# ConnectorsAndProtection.net
KiCad netlist of a schematic drawn in Altium Designer
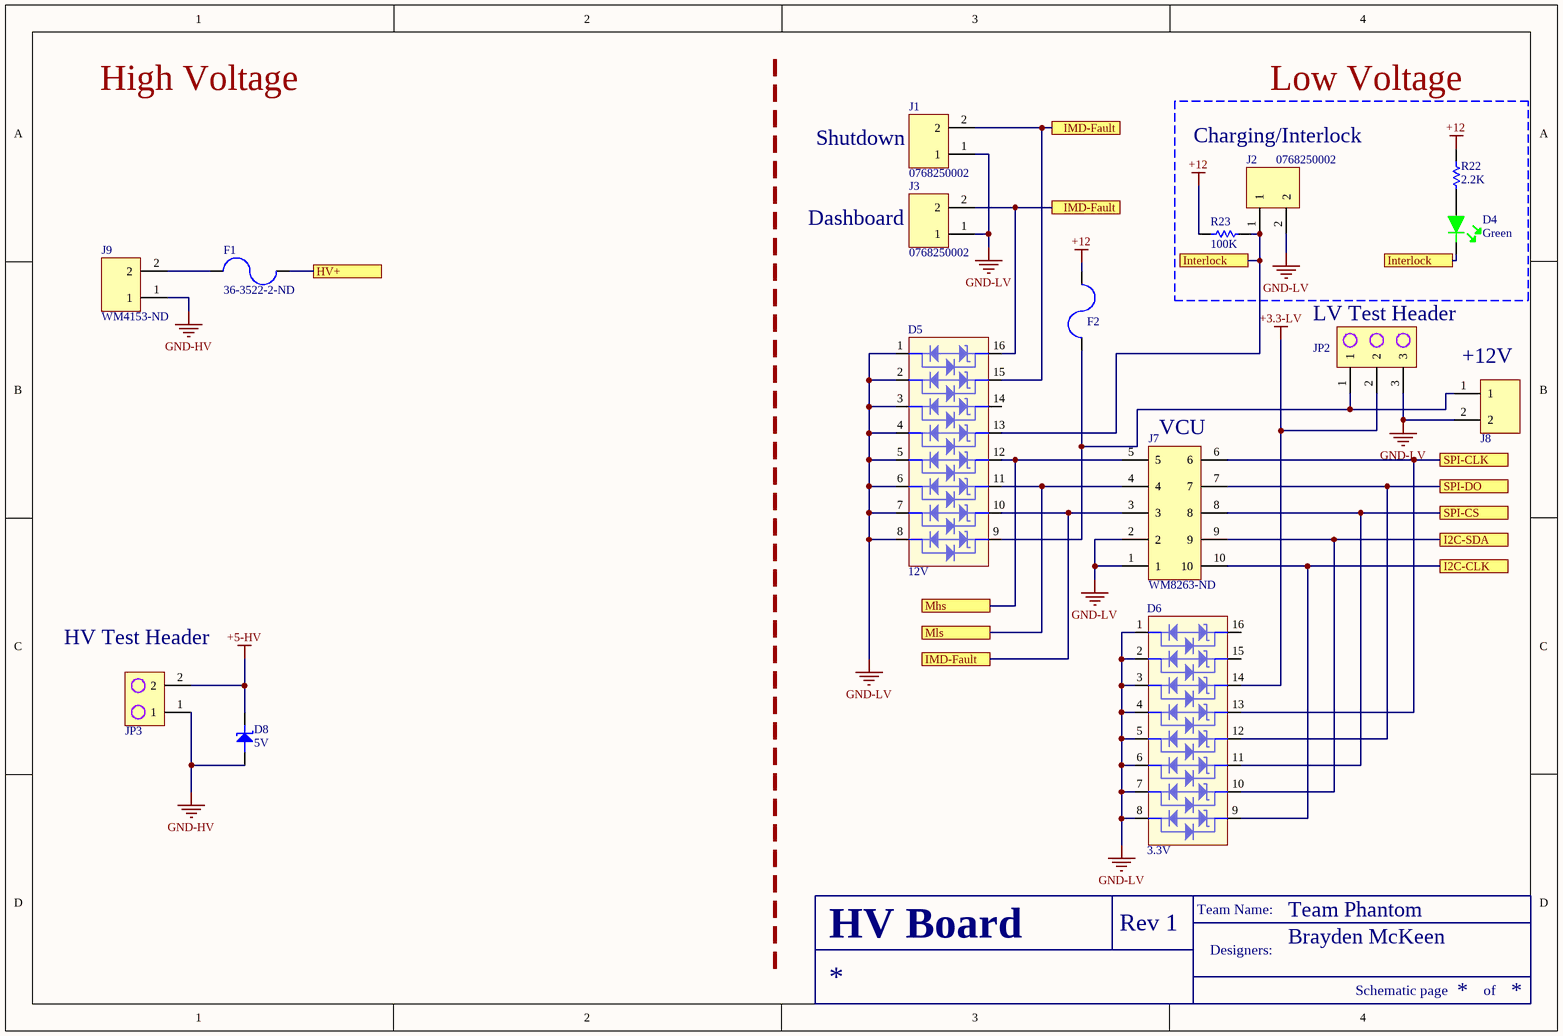
[diagram p0: ConnectorsAndProtection.SchDoc]

(export (version "E")
  (design (tool "Eeschema 10.0.6"))
  (components
    (comp (ref "D4")
      (value "Green")
      (footprint "LED-0603")
      (description "LED GREEN CLEAR 0603 SMD")
      (fields
        (field (name "MANUFACTURER") "Wurth Electronics")
        (field (name "MANUFACTURER PART NUMBER") "150060VS75000")
      )
      (libsource (lib "LEDs") (part "LED-Green"))
    )
    (comp (ref "D5")
      (value "12V")
      (footprint "16-SO")
      (description "PD 300W VWM 12VCJ 25PFPACKAGE SO")
      (libsource (lib "Diodes") (part "TVS-12V-X8"))
    )
    (comp (ref "D6")
      (value "3.3V")
      (footprint "16-SO")
      (description "PD 300W VWM 3.3VCJ 25PFPACKAGE S")
      (libsource (lib "Diodes") (part "TVS-3.3V-X8"))
    )
    (comp (ref "D8")
      (value "5V")
      (footprint "DIODE-SOD323")
      (description "TVS DIODE 5V SOD323")
      (fields
        (field (name "MANUFACTURER") "Nexperia")
        (field (name "MANUFACTURER PART NUMBER") "PESD5V0U1UA,115")
      )
      (libsource (lib "Diodes") (part "TVS-5V"))
    )
    (comp (ref "F1")
      (value "36-3522-2-ND")
      (footprint "Fuse Holder - 500V - 20A")
      (description "FUSE CLIP BLADE 500V 20A PCB")
      (libsource (lib "Misc") (part "Fuse Holder - 500V - 20A"))
    )
    (comp (ref "F2")
      (value "36-3555-2-ND")
      (footprint "Fuse Holder - 500V - 50A")
      (description "FUSE BLOCK BLADE 500V 50A PCB")
      (libsource (lib "Misc") (part "Fuse Holder - 500V - 50A"))
    )
    (comp (ref "J1")
      (value "0768250002")
      (footprint "2X1PIN")
      (description "CONN HEADER R/A 2POS")
      (fields (field (name "MANUFACTURER") "Molex") (field (name "MANUFACTURER PART NUMBER") "76825-0002"))
      (libsource (lib "Connectors") (part "2X1PIN"))
    )
    (comp (ref "J2")
      (value "0768250002")
      (footprint "2X1PIN")
      (description "CONN HEADER R/A 2POS")
      (fields (field (name "MANUFACTURER") "Molex") (field (name "MANUFACTURER PART NUMBER") "76825-0002"))
      (libsource (lib "") (part "2X1PIN_1"))
    )
    (comp (ref "J3")
      (value "0768250002")
      (footprint "2X1PIN")
      (description "CONN HEADER R/A 2POS")
      (fields (field (name "MANUFACTURER") "Molex") (field (name "MANUFACTURER PART NUMBER") "76825-0002"))
      (libsource (lib "Connectors") (part "2X1PIN"))
    )
    (comp (ref "J7")
      (value "WM8263-ND")
      (footprint "2X5PIN")
      (description "CONN HEADER R/A 10POS 2.54MM")
      (fields (field (name "MANUFACTURER") "Molex") (field (name "MANUFACTURER PART NUMBER") "90130-3110"))
      (libsource (lib "Connectors") (part "2X5PIN"))
    )
    (comp (ref "J8")
      (value "952-2900-ND")
      (footprint "2Pin-POWER")
      (description "CONN HEADER VERT 2POS 4MM 800V 40A")
      (libsource (lib "Connectors") (part "2PIN-POWER"))
    )
    (comp (ref "J9")
      (value "WM4153-ND")
      (footprint "2PIN")
      (description "CONN HEADER R/A 2POS 2.54MM")
      (fields (field (name "MANUFACTURER") "Molex") (field (name "MANUFACTURER PART NUMBER") "0705530106"))
      (libsource (lib "Connectors") (part "2PIN"))
    )
    (comp (ref "JP2")
      (value "732-5316-ND")
      (footprint "3PIN-JP")
      (description "CONN HEADER VERT 3POS 2.54MM")
      (libsource (lib "Connectors") (part "3PIN-TEST"))
    )
    (comp (ref "JP3")
      (value "732-5315-ND")
      (footprint "2PIN-JP")
      (description "CONN HEADER VERT 2POS 2.54MM")
      (libsource (lib "Connectors") (part "2PIN-TEST"))
    )
    (comp (ref "R22")
      (value "2.2K")
      (footprint "RES-0805")
      (description "RES SMD 2.2K OHM 1% 1/8W 0805")
      (fields
        (field (name "MANUFACTURER") "Yageo")
        (field (name "MANUFACTURER PART NUMBER") "RC0805FR-072K2L")
      )
      (libsource (lib "Resistors") (part "0805-2.2KR"))
    )
    (comp (ref "R23")
      (value "100K")
      (footprint "RES-0805")
      (description "RES SMD 100K OHM 1% 1/8W 0805")
      (fields
        (field (name "MANUFACTURER") "Yageo")
        (field (name "MANUFACTURER PART NUMBER") "RC0805FR-07100KL")
      )
      (libsource (lib "Resistors") (part "0805-100KR"))
    )
  )
  (nets
    (net (code "1") (name "+3.3-LV") (class "Default")
      (node (ref "D6") (pin "14") (pinfunction "14_14") (pintype "passive"))
      (node (ref "JP2") (pin "2") (pinfunction "2_2") (pintype "passive"))
    )
    (net (code "2") (name "+5-HV") (class "Default")
      (node (ref "D8") (pin "1") (pinfunction "1_1") (pintype "passive"))
      (node (ref "JP3") (pin "2") (pinfunction "2_2") (pintype "passive"))
    )
    (net (code "3") (name "+12") (class "Default")
      (node (ref "F2") (pin "2") (pinfunction "2_2") (pintype "passive"))
      (node (ref "R22") (pin "1") (pinfunction "1_1") (pintype "passive"))
      (node (ref "R23") (pin "1") (pinfunction "1_1") (pintype "passive"))
    )
    (net (code "4") (name "/HV+") (class "Default")
      (node (ref "F1") (pin "2") (pinfunction "2_2") (pintype "passive"))
    )
    (net (code "5") (name "/I2C-CLK") (class "Default")
      (node (ref "D6") (pin "9") (pinfunction "9_9") (pintype "passive"))
      (node (ref "J7") (pin "10") (pinfunction "10_10") (pintype "passive"))
    )
    (net (code "6") (name "/I2C-SDA") (class "Default")
      (node (ref "D6") (pin "10") (pinfunction "10_10") (pintype "passive"))
      (node (ref "J7") (pin "9") (pinfunction "9_9") (pintype "passive"))
    )
    (net (code "7") (name "/IMD-Fault") (class "Default")
      (node (ref "D5") (pin "10") (pinfunction "10_10") (pintype "passive"))
      (node (ref "D5") (pin "15") (pinfunction "15_15") (pintype "passive"))
      (node (ref "D5") (pin "16") (pinfunction "16_16") (pintype "passive"))
      (node (ref "J1") (pin "2") (pinfunction "2_2") (pintype "passive"))
      (node (ref "J3") (pin "2") (pinfunction "2_2") (pintype "passive"))
      (node (ref "J7") (pin "3") (pinfunction "3_3") (pintype "passive"))
    )
    (net (code "8") (name "/Interlock") (class "Default")
      (node (ref "D4") (pin "2") (pinfunction "2_2") (pintype "passive"))
      (node (ref "D5") (pin "13") (pinfunction "13_13") (pintype "passive"))
      (node (ref "J2") (pin "1") (pinfunction "1_1") (pintype "passive"))
      (node (ref "R23") (pin "2") (pinfunction "2_2") (pintype "passive"))
    )
    (net (code "9") (name "/Mhs") (class "Default")
      (node (ref "D5") (pin "12") (pinfunction "12_12") (pintype "passive"))
      (node (ref "J7") (pin "5") (pinfunction "5_5") (pintype "passive"))
    )
    (net (code "10") (name "/Mls") (class "Default")
      (node (ref "D5") (pin "11") (pinfunction "11_11") (pintype "passive"))
      (node (ref "J7") (pin "4") (pinfunction "4_4") (pintype "passive"))
    )
    (net (code "11") (name "/SPI-CLK") (class "Default")
      (node (ref "D6") (pin "13") (pinfunction "13_13") (pintype "passive"))
      (node (ref "J7") (pin "6") (pinfunction "6_6") (pintype "passive"))
    )
    (net (code "12") (name "/SPI-CS") (class "Default")
      (node (ref "D6") (pin "11") (pinfunction "11_11") (pintype "passive"))
      (node (ref "J7") (pin "8") (pinfunction "8_8") (pintype "passive"))
    )
    (net (code "13") (name "/SPI-DO") (class "Default")
      (node (ref "D6") (pin "12") (pinfunction "12_12") (pintype "passive"))
      (node (ref "J7") (pin "7") (pinfunction "7_7") (pintype "passive"))
    )
    (net (code "14") (name "GND-HV") (class "Default")
      (node (ref "D8") (pin "2") (pinfunction "2_2") (pintype "passive"))
      (node (ref "J9") (pin "1") (pinfunction "1_1") (pintype "passive"))
      (node (ref "JP3") (pin "1") (pinfunction "1_1") (pintype "passive"))
    )
    (net (code "15") (name "GND-LV") (class "Default")
      (node (ref "D5") (pin "1") (pinfunction "1_1") (pintype "passive"))
      (node (ref "D5") (pin "2") (pinfunction "2_2") (pintype "passive"))
      (node (ref "D5") (pin "3") (pinfunction "3_3") (pintype "passive"))
      (node (ref "D5") (pin "4") (pinfunction "4_4") (pintype "passive"))
      (node (ref "D5") (pin "5") (pinfunction "5_5") (pintype "passive"))
      (node (ref "D5") (pin "6") (pinfunction "6_6") (pintype "passive"))
      (node (ref "D5") (pin "7") (pinfunction "7_7") (pintype "passive"))
      (node (ref "D5") (pin "8") (pinfunction "8_8") (pintype "passive"))
      (node (ref "D6") (pin "1") (pinfunction "1_1") (pintype "passive"))
      (node (ref "D6") (pin "2") (pinfunction "2_2") (pintype "passive"))
      (node (ref "D6") (pin "3") (pinfunction "3_3") (pintype "passive"))
      (node (ref "D6") (pin "4") (pinfunction "4_4") (pintype "passive"))
      (node (ref "D6") (pin "5") (pinfunction "5_5") (pintype "passive"))
      (node (ref "D6") (pin "6") (pinfunction "6_6") (pintype "passive"))
      (node (ref "D6") (pin "7") (pinfunction "7_7") (pintype "passive"))
      (node (ref "D6") (pin "8") (pinfunction "8_8") (pintype "passive"))
      (node (ref "J1") (pin "1") (pinfunction "1_1") (pintype "passive"))
      (node (ref "J2") (pin "2") (pinfunction "2_2") (pintype "passive"))
      (node (ref "J3") (pin "1") (pinfunction "1_1") (pintype "passive"))
      (node (ref "J7") (pin "1") (pinfunction "1_1") (pintype "passive"))
      (node (ref "J7") (pin "2") (pinfunction "2_2") (pintype "passive"))
      (node (ref "J8") (pin "2") (pinfunction "2_2") (pintype "passive"))
      (node (ref "JP2") (pin "3") (pinfunction "3_3") (pintype "passive"))
    )
    (net (code "16") (name "Net-(D4-Pad1)") (class "Default")
      (node (ref "D4") (pin "1") (pinfunction "1_1") (pintype "passive"))
      (node (ref "R22") (pin "2") (pinfunction "2_2") (pintype "passive"))
    )
    (net (code "17") (name "Net-(D5-Pad9)") (class "Default")
      (node (ref "D5") (pin "9") (pinfunction "9_9") (pintype "passive"))
      (node (ref "F2") (pin "1") (pinfunction "1_1") (pintype "passive"))
      (node (ref "J8") (pin "1") (pinfunction "1_1") (pintype "passive"))
      (node (ref "JP2") (pin "1") (pinfunction "1_1") (pintype "passive"))
    )
    (net (code "18") (name "Net-(F1-Pad1)") (class "Default")
      (node (ref "F1") (pin "1") (pinfunction "1_1") (pintype "passive"))
      (node (ref "J9") (pin "2") (pinfunction "2_2") (pintype "passive"))
    )
    (net (code "19") (name "unconnected-(D5-Pad14)") (class "Default")
      (node (ref "D5") (pin "14") (pinfunction "14_14") (pintype "passive"))
    )
    (net (code "20") (name "unconnected-(D6-Pad15)") (class "Default")
      (node (ref "D6") (pin "15") (pinfunction "15_15") (pintype "passive"))
    )
    (net (code "21") (name "unconnected-(D6-Pad16)") (class "Default")
      (node (ref "D6") (pin "16") (pinfunction "16_16") (pintype "passive"))
    )
  )
)
